# dep-switch-TPS22959DNYT.net
KiCad netlist of a schematic drawn in Altium Designer
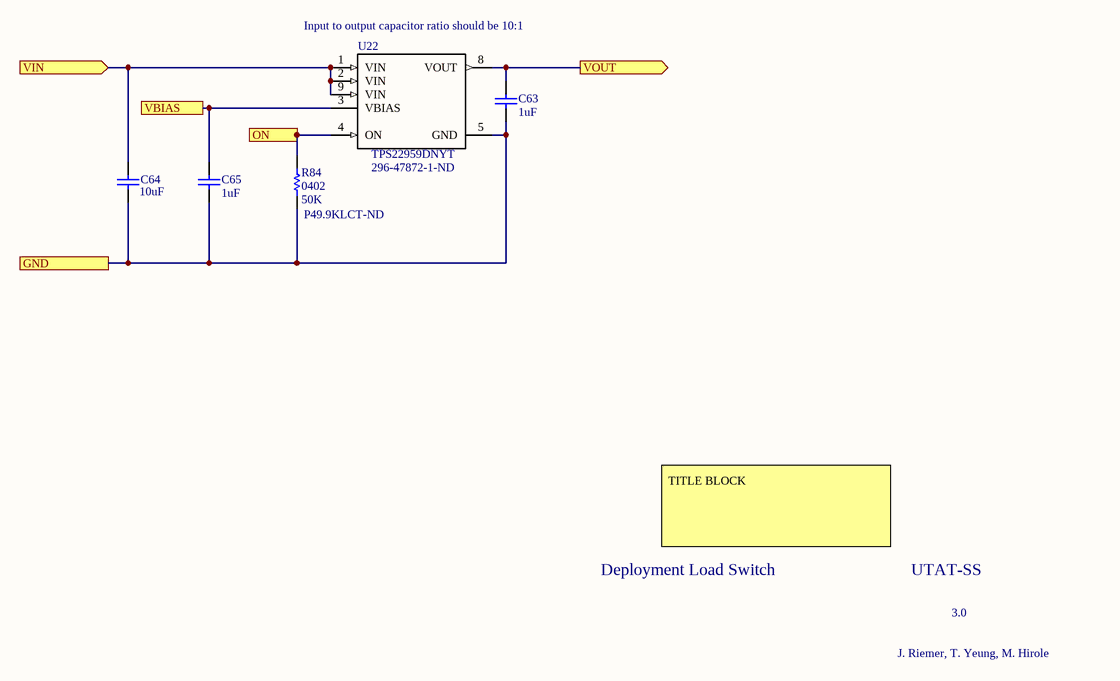
[diagram p0: dep-switch-TPS22959DNYT.SchDoc]

(export (version "E")
  (design (tool "Eeschema 10.0.6"))
  (components
    (comp (ref "C63")
      (value "1uF")
      (footprint "CAP0603R")
      (description "0603 capacitor")
      (fields (field (name "Comment") "0603"))
      (libsource (lib "heron-general") (part "CAP0603"))
    )
    (comp (ref "C64")
      (value "10uF")
      (footprint "CAP0805R")
      (description "0805 capacitor")
      (fields (field (name "Comment") "0805"))
      (libsource (lib "heron-general") (part "CAP0805"))
    )
    (comp (ref "C65")
      (value "1uF")
      (footprint "CAP0603R")
      (description "0603 capacitor")
      (fields (field (name "Comment") "0603"))
      (libsource (lib "heron-general") (part "CAP0603"))
    )
    (comp (ref "R84")
      (value "0402")
      (footprint "RES0402R")
      (description "0402 resistor")
      (fields
        (field (name "ALTIUM_VALUE") "50K")
        (field (name "SUPPLIER PART NUMBER 1") "P49.9KLCT-ND")
        (field (name "MANUFACTURER") "Panasonic")
        (field (name "MANUFACTURER PART NUMBER") "ERJ-2RKF4992X")
      )
      (libsource (lib "heron-general") (part "RES0402"))
    )
    (comp (ref "U22")
      (value "TPS22959DNYT")
      (footprint "TPS22959DNYT")
      (description "5.5V, 15A, 4.4mÎ© Load Switch with Quick Output Discharge 8-WSON -40 to 85")
      (fields
        (field (name "MF") "Texas Instruments")
        (field (name "DIGI-KEY_PART_NUMBER") "296-47872-1-ND")
        (field (name "SUPPLIER PART NUMBER 1") "296-47872-1-ND")
      )
      (libsource (lib "heron-general") (part "TPS22959DNYT"))
    )
  )
  (nets
    (net (code "1") (name "/GND") (class "Default")
      (node (ref "C63") (pin "1") (pinfunction "1_1") (pintype "passive"))
      (node (ref "C64") (pin "1") (pinfunction "1_1") (pintype "passive"))
      (node (ref "C65") (pin "1") (pinfunction "1_1") (pintype "passive"))
      (node (ref "R84") (pin "1") (pinfunction "1_1") (pintype "passive"))
      (node (ref "U22") (pin "5") (pinfunction "GND_5") (pintype "power_in"))
    )
    (net (code "2") (name "/ON") (class "Default")
      (node (ref "R84") (pin "2") (pinfunction "2_2") (pintype "passive"))
      (node (ref "U22") (pin "4") (pinfunction "ON_4") (pintype "input"))
    )
    (net (code "3") (name "/VBIAS") (class "Default")
      (node (ref "C65") (pin "2") (pinfunction "2_2") (pintype "passive"))
      (node (ref "U22") (pin "3") (pinfunction "VBIAS_3") (pintype "power_in"))
    )
    (net (code "4") (name "/VIN") (class "Default")
      (node (ref "C64") (pin "2") (pinfunction "2_2") (pintype "passive"))
      (node (ref "U22") (pin "1") (pinfunction "VIN_1") (pintype "input"))
      (node (ref "U22") (pin "2") (pinfunction "VIN_2") (pintype "input"))
      (node (ref "U22") (pin "9") (pinfunction "VIN_9") (pintype "input"))
    )
    (net (code "5") (name "/VOUT") (class "Default")
      (node (ref "C63") (pin "2") (pinfunction "2_2") (pintype "passive"))
      (node (ref "U22") (pin "8") (pinfunction "VOUT_8") (pintype "output"))
    )
  )
)
